# ears_v40.net
KiCad netlist of a schematic drawn in EAGLE
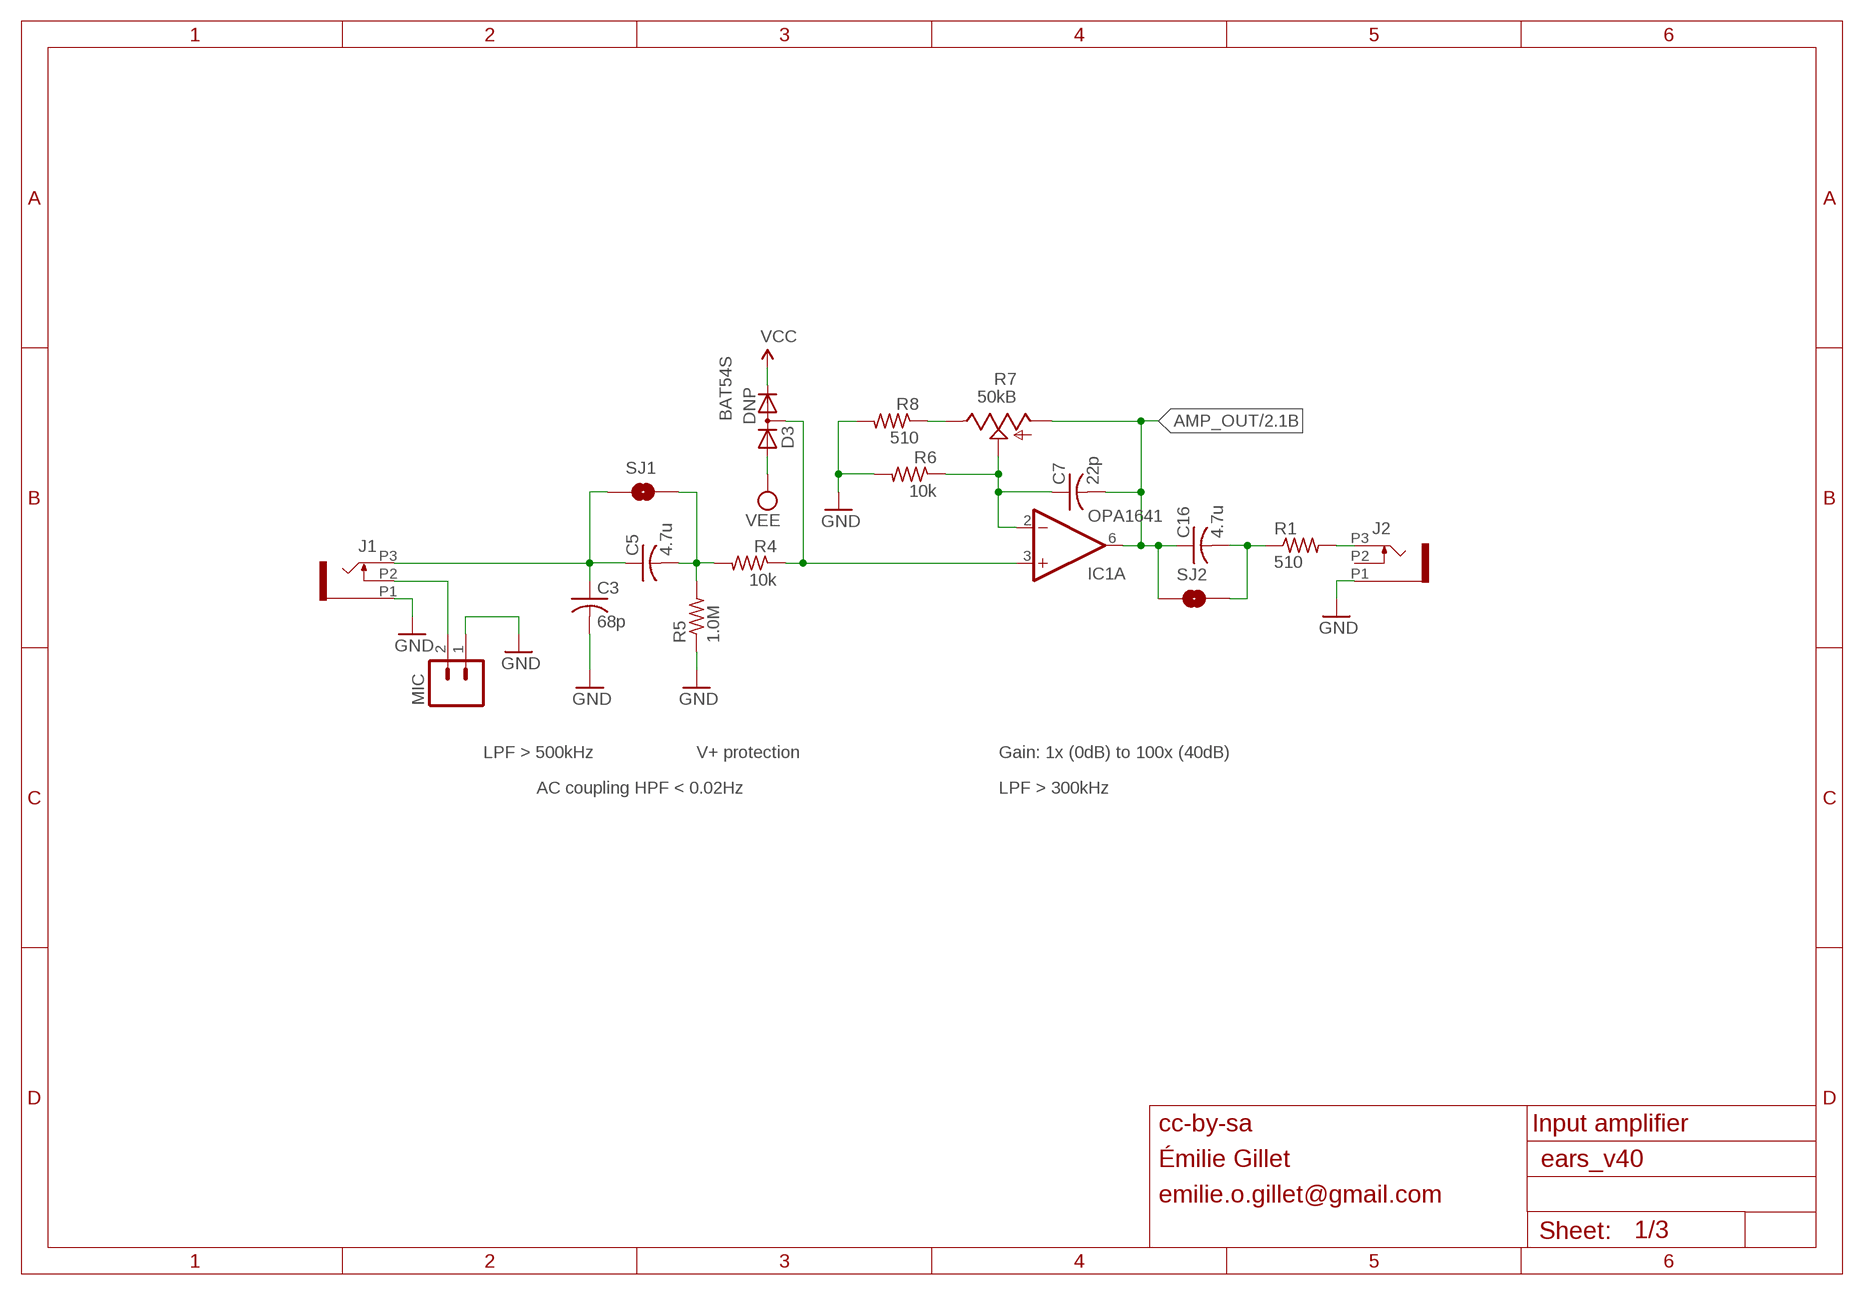
[diagram p0: schematic, sheet 1]
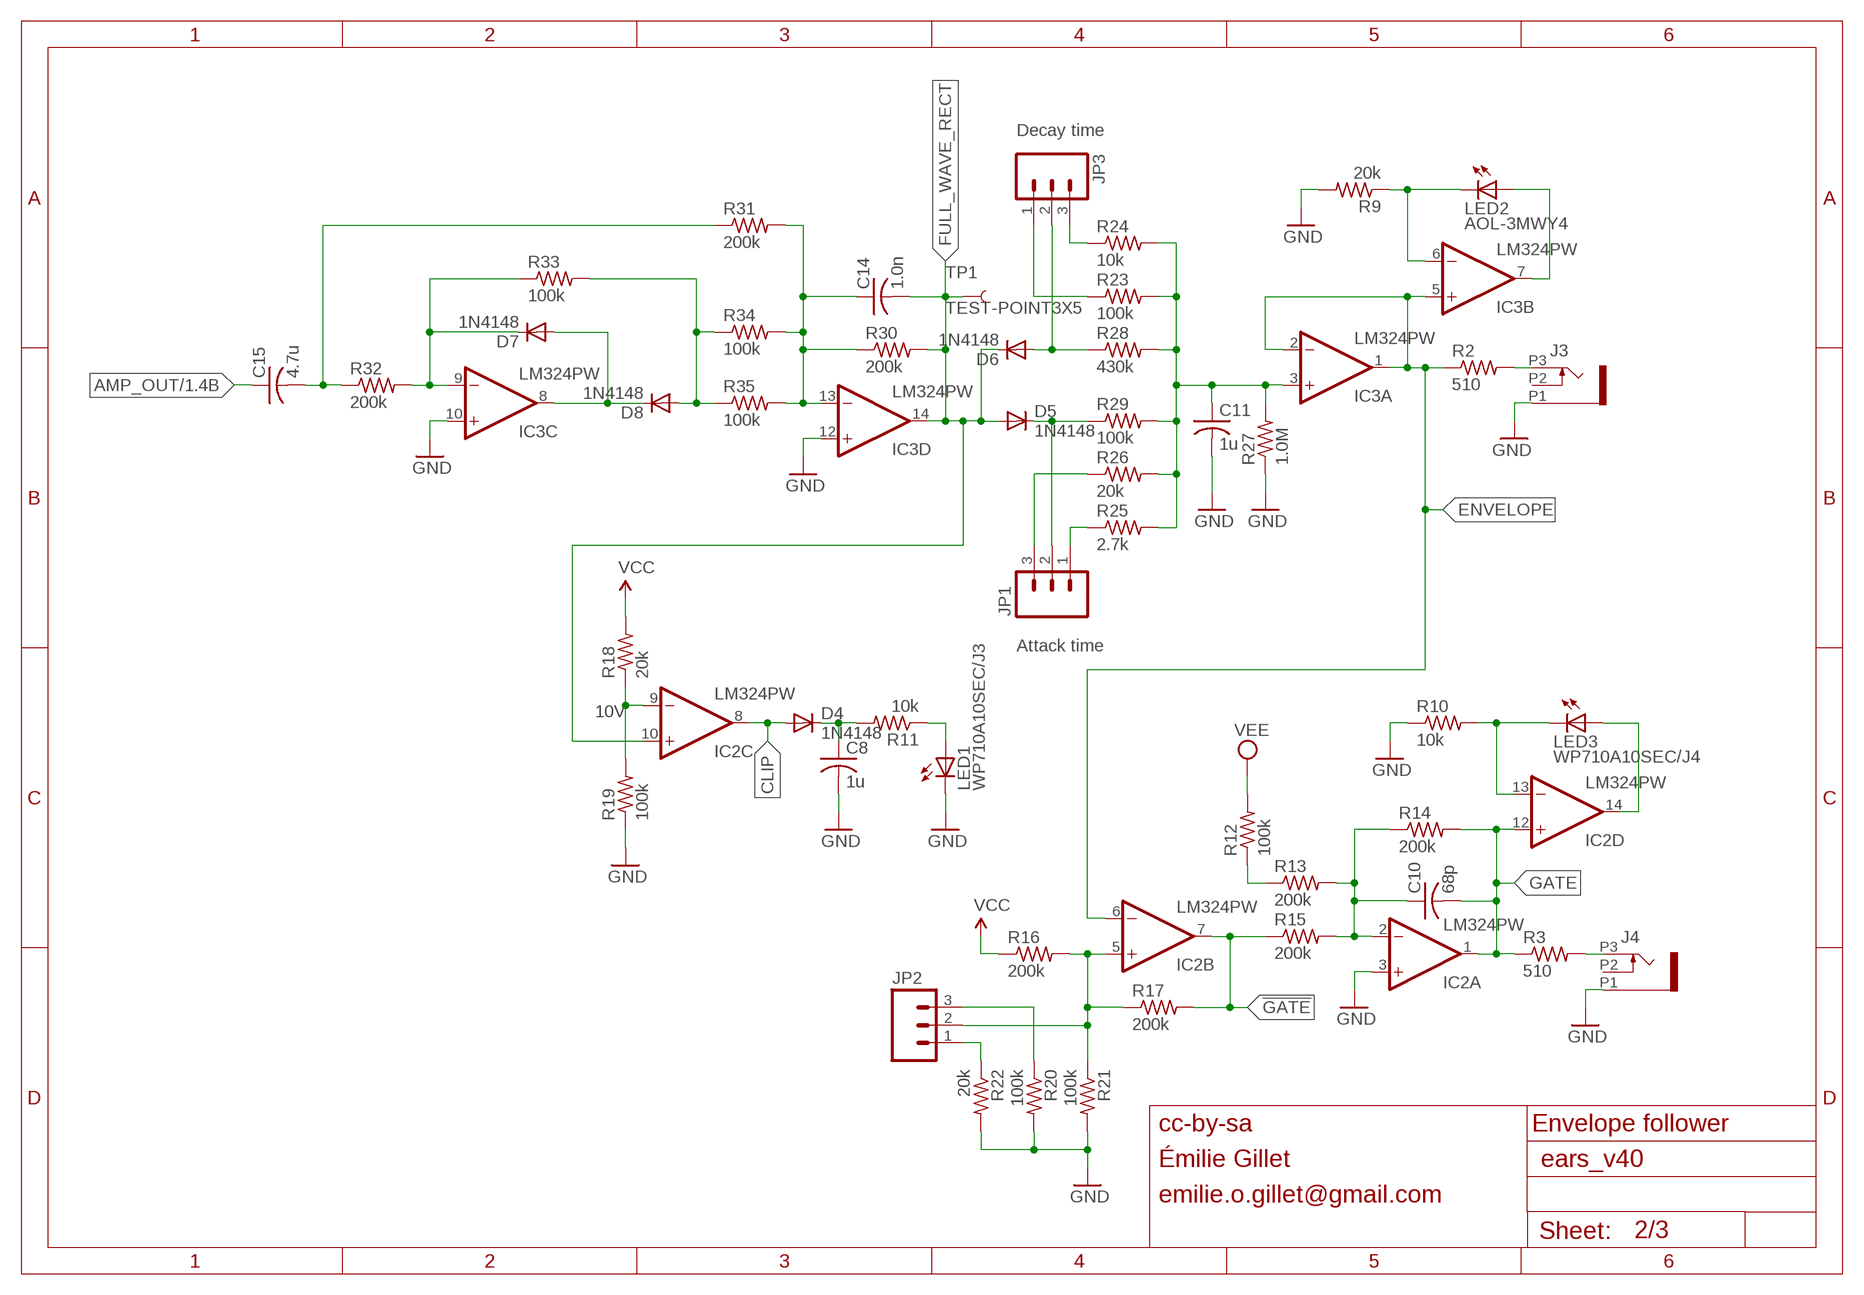
[diagram p1: schematic, sheet 2]
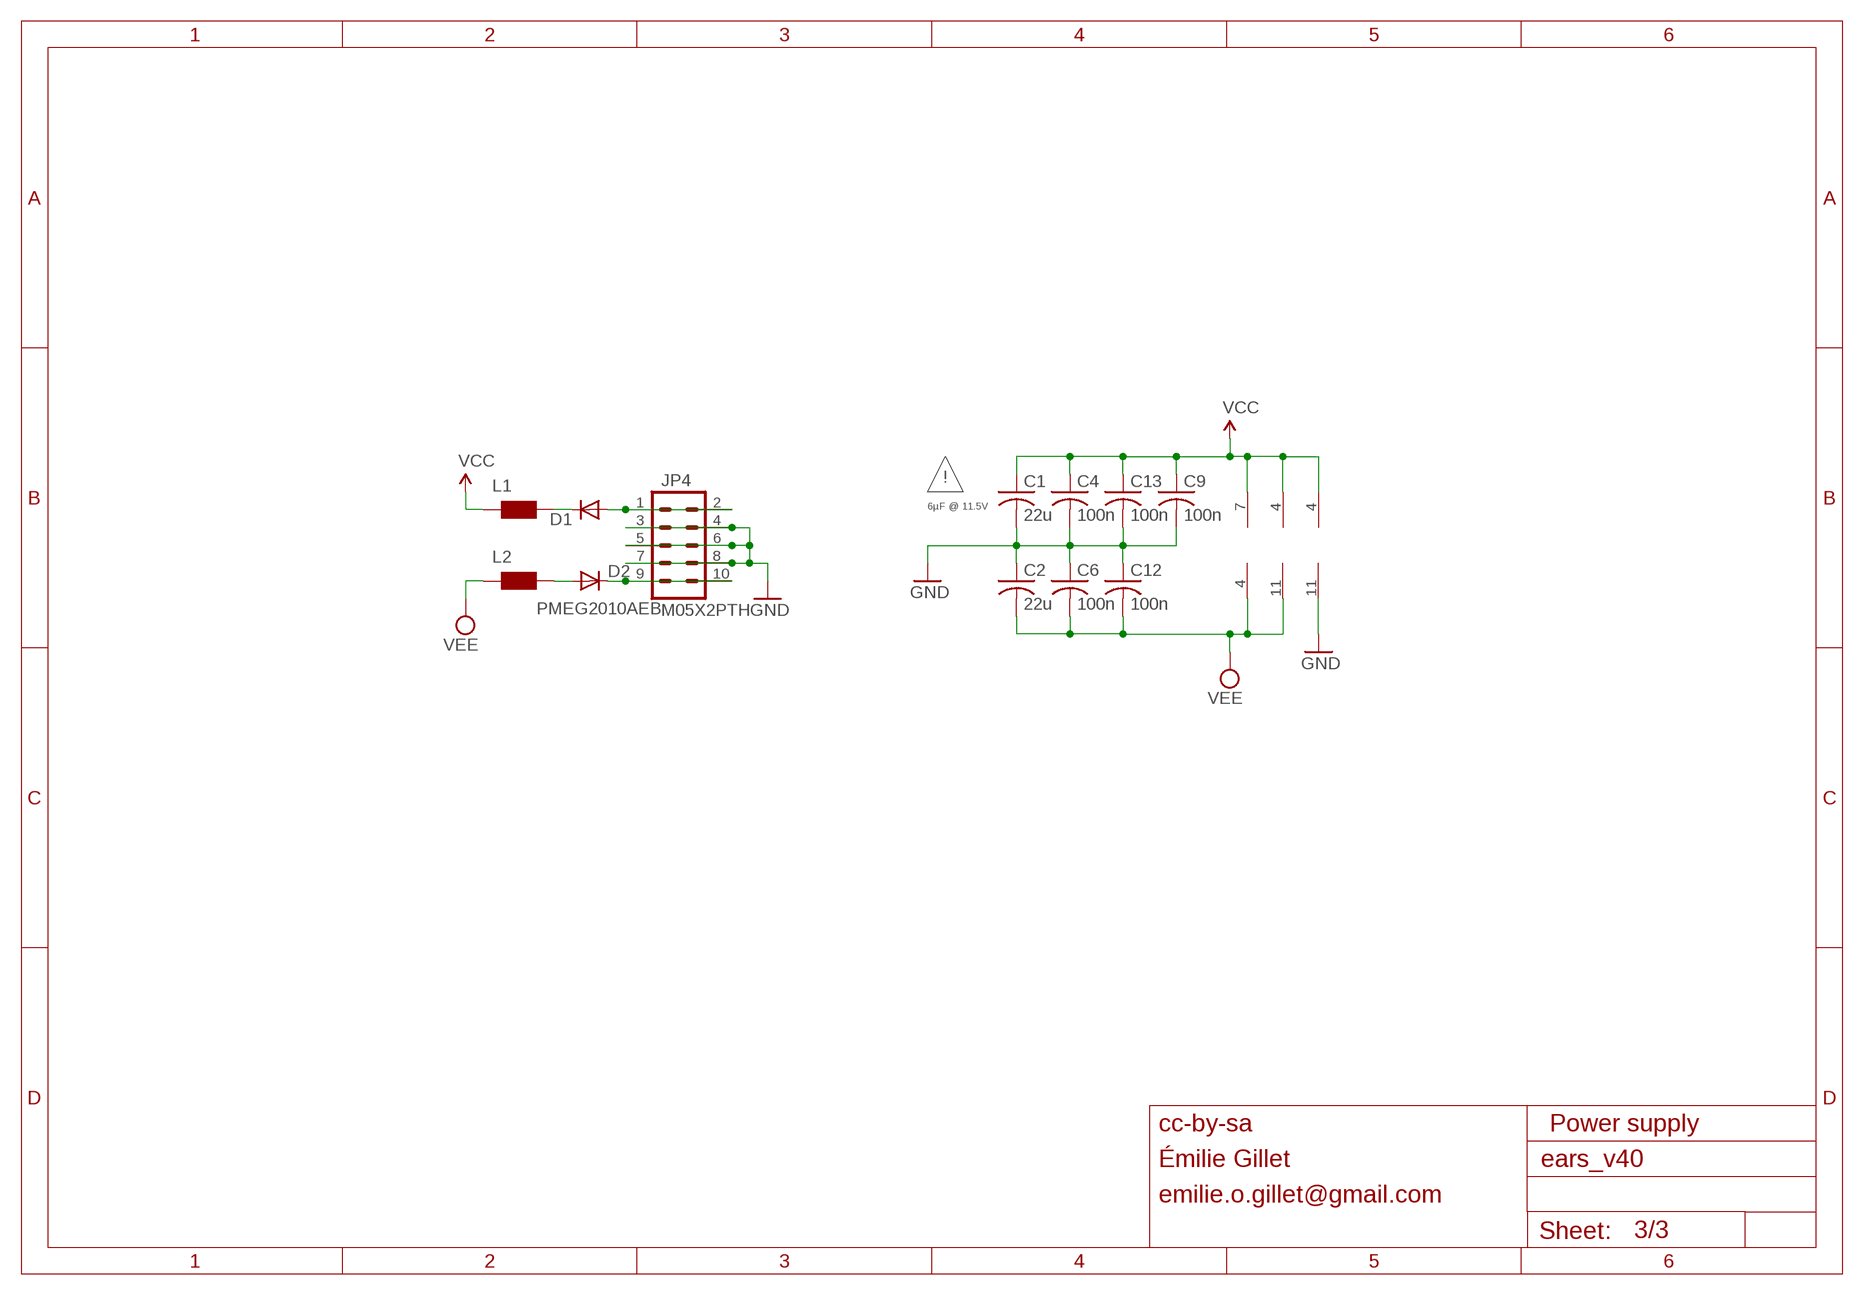
[diagram p2: schematic, sheet 3]

(export (version "E")
  (design (tool "Eeschema 10.0.6"))
  (components
    (comp (ref "C3")
      (value "68p")
      (footprint "eagle-import:C0402")
      (libsource (lib "eagle-import") (part "C-USC0402"))
    )
    (comp (ref "C5")
      (value "4.7u")
      (footprint "eagle-import:C0603")
      (libsource (lib "eagle-import") (part "C-USC0603"))
    )
    (comp (ref "C7")
      (value "22p")
      (footprint "eagle-import:C0402")
      (libsource (lib "eagle-import") (part "C-USC0402"))
    )
    (comp (ref "C16")
      (value "4.7u")
      (footprint "eagle-import:C0603")
      (libsource (lib "eagle-import") (part "C-USC0603"))
    )
    (comp (ref "D3")
      (value "DNP")
      (footprint "eagle-import:SOT23")
      (libsource (lib "eagle-import") (part "DIODE_2CACA-SOT23"))
    )
    (comp (ref "IC1")
      (value "OPA1641")
      (footprint "eagle-import:MSOP8")
      (libsource (lib "eagle-import") (part "OPA1641"))
    )
    (comp (ref "J1")
      (value "PJ301_THONKICONN6")
      (footprint "eagle-import:WQP_PJ_301M6")
      (libsource (lib "eagle-import") (part "PJ301_THONKICONN6"))
    )
    (comp (ref "J2")
      (value "PJ301_THONKICONN6")
      (footprint "eagle-import:WQP_PJ_301M6")
      (libsource (lib "eagle-import") (part "PJ301_THONKICONN6"))
    )
    (comp (ref "MIC")
      (value "M02TINY")
      (footprint "eagle-import:1X02_TINY")
      (libsource (lib "eagle-import") (part "M02TINY"))
    )
    (comp (ref "R1")
      (value "510")
      (footprint "eagle-import:R0402")
      (libsource (lib "eagle-import") (part "R-US_R0402"))
    )
    (comp (ref "R4")
      (value "10k")
      (footprint "eagle-import:R0402")
      (libsource (lib "eagle-import") (part "R-US_R0402"))
    )
    (comp (ref "R5")
      (value "1.0M")
      (footprint "eagle-import:R0402")
      (libsource (lib "eagle-import") (part "R-US_R0402"))
    )
    (comp (ref "R6")
      (value "10k")
      (footprint "eagle-import:R0402")
      (libsource (lib "eagle-import") (part "R-US_R0402"))
    )
    (comp (ref "R7")
      (value "50kB")
      (footprint "eagle-import:ALPS_POT_VERTICAL_PS")
      (libsource (lib "eagle-import") (part "POT_USVERTICAL_PS"))
    )
    (comp (ref "R8")
      (value "510")
      (footprint "eagle-import:R0402")
      (libsource (lib "eagle-import") (part "R-US_R0402"))
    )
    (comp (ref "SJ1")
      (value "SOLDERJUMPERNC")
      (footprint "eagle-import:SJ_2S")
      (libsource (lib "eagle-import") (part "SOLDERJUMPERNC"))
    )
    (comp (ref "SJ2")
      (value "SOLDERJUMPERNC")
      (footprint "eagle-import:SJ_2S")
      (libsource (lib "eagle-import") (part "SOLDERJUMPERNC"))
    )
    (comp (ref "C8")
      (value "1u")
      (footprint "eagle-import:C0402")
      (libsource (lib "eagle-import") (part "C-USC0402"))
    )
    (comp (ref "C10")
      (value "68p")
      (footprint "eagle-import:C0402")
      (libsource (lib "eagle-import") (part "C-USC0402"))
    )
    (comp (ref "C11")
      (value "1u")
      (footprint "eagle-import:C0402")
      (libsource (lib "eagle-import") (part "C-USC0402"))
    )
    (comp (ref "C14")
      (value "1.0n")
      (footprint "eagle-import:C0402")
      (libsource (lib "eagle-import") (part "C-USC0402"))
    )
    (comp (ref "C15")
      (value "4.7u")
      (footprint "eagle-import:C0603")
      (libsource (lib "eagle-import") (part "C-USC0603"))
    )
    (comp (ref "D4")
      (value "1N4148")
      (footprint "eagle-import:SOD523")
      (libsource (lib "eagle-import") (part "DIODE-SOD523"))
    )
    (comp (ref "D5")
      (value "1N4148")
      (footprint "eagle-import:SOD523")
      (libsource (lib "eagle-import") (part "DIODE-SOD523"))
    )
    (comp (ref "D6")
      (value "1N4148")
      (footprint "eagle-import:SOD523")
      (libsource (lib "eagle-import") (part "DIODE-SOD523"))
    )
    (comp (ref "D7")
      (value "1N4148")
      (footprint "eagle-import:SOD523")
      (libsource (lib "eagle-import") (part "DIODE-SOD523"))
    )
    (comp (ref "D8")
      (value "1N4148")
      (footprint "eagle-import:SOD523")
      (libsource (lib "eagle-import") (part "DIODE-SOD523"))
    )
    (comp (ref "IC2")
      (value "LM324PW")
      (footprint "eagle-import:TSSOP14")
      (libsource (lib "eagle-import") (part "LM324PW"))
    )
    (comp (ref "IC3")
      (value "LM324PW")
      (footprint "eagle-import:TSSOP14")
      (libsource (lib "eagle-import") (part "LM324PW"))
    )
    (comp (ref "J3")
      (value "PJ301_THONKICONN6")
      (footprint "eagle-import:WQP_PJ_301M6")
      (libsource (lib "eagle-import") (part "PJ301_THONKICONN6"))
    )
    (comp (ref "J4")
      (value "PJ301_THONKICONN6")
      (footprint "eagle-import:WQP_PJ_301M6")
      (libsource (lib "eagle-import") (part "PJ301_THONKICONN6"))
    )
    (comp (ref "JP1")
      (value "M03PTH")
      (footprint "eagle-import:1X03")
      (libsource (lib "eagle-import") (part "M03PTH"))
    )
    (comp (ref "JP2")
      (value "M03PTH")
      (footprint "eagle-import:1X03")
      (libsource (lib "eagle-import") (part "M03PTH"))
    )
    (comp (ref "JP3")
      (value "M03PTH")
      (footprint "eagle-import:1X03")
      (libsource (lib "eagle-import") (part "M03PTH"))
    )
    (comp (ref "LED1")
      (value "WP710A10SEC/J3")
      (footprint "eagle-import:LED3MM")
      (libsource (lib "eagle-import") (part "LED3MM"))
    )
    (comp (ref "LED2")
      (value "AOL-3MWY4")
      (footprint "eagle-import:LED3MM")
      (libsource (lib "eagle-import") (part "LED3MM"))
    )
    (comp (ref "LED3")
      (value "WP710A10SEC/J4")
      (footprint "eagle-import:LED3MM")
      (libsource (lib "eagle-import") (part "LED3MM"))
    )
    (comp (ref "R2")
      (value "510")
      (footprint "eagle-import:R0402")
      (libsource (lib "eagle-import") (part "R-US_R0402"))
    )
    (comp (ref "R3")
      (value "510")
      (footprint "eagle-import:R0402")
      (libsource (lib "eagle-import") (part "R-US_R0402"))
    )
    (comp (ref "R9")
      (value "20k")
      (footprint "eagle-import:R0402")
      (libsource (lib "eagle-import") (part "R-US_R0402"))
    )
    (comp (ref "R10")
      (value "10k")
      (footprint "eagle-import:R0402")
      (libsource (lib "eagle-import") (part "R-US_R0402"))
    )
    (comp (ref "R11")
      (value "10k")
      (footprint "eagle-import:R0402")
      (libsource (lib "eagle-import") (part "R-US_R0402"))
    )
    (comp (ref "R12")
      (value "100k")
      (footprint "eagle-import:R0402")
      (libsource (lib "eagle-import") (part "R-US_R0402"))
    )
    (comp (ref "R13")
      (value "200k")
      (footprint "eagle-import:R0402")
      (libsource (lib "eagle-import") (part "R-US_R0402"))
    )
    (comp (ref "R14")
      (value "200k")
      (footprint "eagle-import:R0402")
      (libsource (lib "eagle-import") (part "R-US_R0402"))
    )
    (comp (ref "R15")
      (value "200k")
      (footprint "eagle-import:R0402")
      (libsource (lib "eagle-import") (part "R-US_R0402"))
    )
    (comp (ref "R16")
      (value "200k")
      (footprint "eagle-import:R0402")
      (libsource (lib "eagle-import") (part "R-US_R0402"))
    )
    (comp (ref "R17")
      (value "200k")
      (footprint "eagle-import:R0402")
      (libsource (lib "eagle-import") (part "R-US_R0402"))
    )
    (comp (ref "R18")
      (value "20k")
      (footprint "eagle-import:R0402")
      (libsource (lib "eagle-import") (part "R-US_R0402"))
    )
    (comp (ref "R19")
      (value "100k")
      (footprint "eagle-import:R0402")
      (libsource (lib "eagle-import") (part "R-US_R0402"))
    )
    (comp (ref "R20")
      (value "100k")
      (footprint "eagle-import:R0402")
      (libsource (lib "eagle-import") (part "R-US_R0402"))
    )
    (comp (ref "R21")
      (value "100k")
      (footprint "eagle-import:R0402")
      (libsource (lib "eagle-import") (part "R-US_R0402"))
    )
    (comp (ref "R22")
      (value "20k")
      (footprint "eagle-import:R0402")
      (libsource (lib "eagle-import") (part "R-US_R0402"))
    )
    (comp (ref "R23")
      (value "100k")
      (footprint "eagle-import:R0402")
      (libsource (lib "eagle-import") (part "R-US_R0402"))
    )
    (comp (ref "R24")
      (value "10k")
      (footprint "eagle-import:R0402")
      (libsource (lib "eagle-import") (part "R-US_R0402"))
    )
    (comp (ref "R25")
      (value "2.7k")
      (footprint "eagle-import:R0402")
      (libsource (lib "eagle-import") (part "R-US_R0402"))
    )
    (comp (ref "R26")
      (value "20k")
      (footprint "eagle-import:R0402")
      (libsource (lib "eagle-import") (part "R-US_R0402"))
    )
    (comp (ref "R27")
      (value "1.0M")
      (footprint "eagle-import:R0402")
      (libsource (lib "eagle-import") (part "R-US_R0402"))
    )
    (comp (ref "R28")
      (value "430k")
      (footprint "eagle-import:R0402")
      (libsource (lib "eagle-import") (part "R-US_R0402"))
    )
    (comp (ref "R29")
      (value "100k")
      (footprint "eagle-import:R0402")
      (libsource (lib "eagle-import") (part "R-US_R0402"))
    )
    (comp (ref "R30")
      (value "200k")
      (footprint "eagle-import:R0402")
      (libsource (lib "eagle-import") (part "R-US_R0402"))
    )
    (comp (ref "R31")
      (value "200k")
      (footprint "eagle-import:R0402")
      (libsource (lib "eagle-import") (part "R-US_R0402"))
    )
    (comp (ref "R32")
      (value "200k")
      (footprint "eagle-import:R0402")
      (libsource (lib "eagle-import") (part "R-US_R0402"))
    )
    (comp (ref "R33")
      (value "100k")
      (footprint "eagle-import:R0402")
      (libsource (lib "eagle-import") (part "R-US_R0402"))
    )
    (comp (ref "R34")
      (value "100k")
      (footprint "eagle-import:R0402")
      (libsource (lib "eagle-import") (part "R-US_R0402"))
    )
    (comp (ref "R35")
      (value "100k")
      (footprint "eagle-import:R0402")
      (libsource (lib "eagle-import") (part "R-US_R0402"))
    )
    (comp (ref "TP1")
      (value "TEST-POINT3X5")
      (footprint "eagle-import:PAD.03X.05")
      (libsource (lib "eagle-import") (part "TEST-POINT3X5"))
    )
    (comp (ref "C1")
      (value "22u")
      (footprint "eagle-import:C1206")
      (libsource (lib "eagle-import") (part "C-USC1206"))
    )
    (comp (ref "C2")
      (value "22u")
      (footprint "eagle-import:C1206")
      (libsource (lib "eagle-import") (part "C-USC1206"))
    )
    (comp (ref "C4")
      (value "100n")
      (footprint "eagle-import:C0402")
      (libsource (lib "eagle-import") (part "C-USC0402"))
    )
    (comp (ref "C6")
      (value "100n")
      (footprint "eagle-import:C0402")
      (libsource (lib "eagle-import") (part "C-USC0402"))
    )
    (comp (ref "C9")
      (value "100n")
      (footprint "eagle-import:C0402")
      (libsource (lib "eagle-import") (part "C-USC0402"))
    )
    (comp (ref "C12")
      (value "100n")
      (footprint "eagle-import:C0402")
      (libsource (lib "eagle-import") (part "C-USC0402"))
    )
    (comp (ref "C13")
      (value "100n")
      (footprint "eagle-import:C0402")
      (libsource (lib "eagle-import") (part "C-USC0402"))
    )
    (comp (ref "D1")
      (value "PMEG2010AEB")
      (footprint "eagle-import:SOD523")
      (libsource (lib "eagle-import") (part "DIODE-SOD523"))
    )
    (comp (ref "D2")
      (value "PMEG2010AEB")
      (footprint "eagle-import:SOD523")
      (libsource (lib "eagle-import") (part "DIODE-SOD523"))
    )
    (comp (ref "JP4")
      (value "M05X2PTH")
      (footprint "eagle-import:AVR_ICSP")
      (libsource (lib "eagle-import") (part "M05X2PTH"))
    )
    (comp (ref "L1")
      (value "WE-CBF_0603")
      (footprint "eagle-import:0603")
      (libsource (lib "eagle-import") (part "WE-CBF_0603"))
    )
    (comp (ref "L2")
      (value "WE-CBF_0603")
      (footprint "eagle-import:0603")
      (libsource (lib "eagle-import") (part "WE-CBF_0603"))
    )
  )
  (nets
    (net (code "1") (name "AMP_OUT") (class "Default")
      (node (ref "C15") (pin "1") (pinfunction "1_1") (pintype "passive"))
      (node (ref "C16") (pin "1") (pinfunction "1_1") (pintype "passive"))
      (node (ref "C7") (pin "2") (pinfunction "2_2") (pintype "passive"))
      (node (ref "IC1") (pin "6") (pinfunction "OUT_6") (pintype "output"))
      (node (ref "R7") (pin "P$3") (pinfunction "A_P$3") (pintype "passive"))
      (node (ref "SJ2") (pin "1") (pinfunction "1_1") (pintype "passive"))
    )
    (net (code "2") (name "CLIP") (class "Default")
      (node (ref "D4") (pin "A") (pinfunction "A_A") (pintype "passive"))
      (node (ref "IC2") (pin "8") (pinfunction "OUT_8") (pintype "output"))
    )
    (net (code "3") (name "ENVELOPE") (class "Default")
      (node (ref "IC2") (pin "6") (pinfunction "-IN_6") (pintype "input"))
      (node (ref "IC3") (pin "1") (pinfunction "OUT_1") (pintype "output"))
      (node (ref "IC3") (pin "2") (pinfunction "-IN_2") (pintype "input"))
      (node (ref "IC3") (pin "5") (pinfunction "+IN_5") (pintype "input"))
      (node (ref "R2") (pin "1") (pinfunction "1_1") (pintype "passive"))
    )
    (net (code "4") (name "FULL_WAVE_RECT") (class "Default")
      (node (ref "C14") (pin "2") (pinfunction "2_2") (pintype "passive"))
      (node (ref "D5") (pin "A") (pinfunction "A_A") (pintype "passive"))
      (node (ref "D6") (pin "C") (pinfunction "C_C") (pintype "passive"))
      (node (ref "IC2") (pin "10") (pinfunction "+IN_10") (pintype "input"))
      (node (ref "IC3") (pin "14") (pinfunction "OUT_14") (pintype "output"))
      (node (ref "R30") (pin "2") (pinfunction "2_2") (pintype "passive"))
      (node (ref "TP1") (pin "P$1") (pinfunction "1_P$1") (pintype "bidirectional"))
    )
    (net (code "5") (name "GATE") (class "Default")
      (node (ref "C10") (pin "2") (pinfunction "2_2") (pintype "passive"))
      (node (ref "IC2") (pin "1") (pinfunction "OUT_1") (pintype "output"))
      (node (ref "IC2") (pin "12") (pinfunction "+IN_12") (pintype "input"))
      (node (ref "R14") (pin "2") (pinfunction "2_2") (pintype "passive"))
      (node (ref "R3") (pin "1") (pinfunction "1_1") (pintype "passive"))
    )
    (net (code "6") (name "GND") (class "Default")
      (node (ref "C1") (pin "2") (pinfunction "2_2") (pintype "passive"))
      (node (ref "C11") (pin "2") (pinfunction "2_2") (pintype "passive"))
      (node (ref "C12") (pin "1") (pinfunction "1_1") (pintype "passive"))
      (node (ref "C13") (pin "2") (pinfunction "2_2") (pintype "passive"))
      (node (ref "C2") (pin "1") (pinfunction "1_1") (pintype "passive"))
      (node (ref "C3") (pin "2") (pinfunction "2_2") (pintype "passive"))
      (node (ref "C4") (pin "2") (pinfunction "2_2") (pintype "passive"))
      (node (ref "C6") (pin "1") (pinfunction "1_1") (pintype "passive"))
      (node (ref "C8") (pin "2") (pinfunction "2_2") (pintype "passive"))
      (node (ref "C9") (pin "2") (pinfunction "2_2") (pintype "passive"))
      (node (ref "IC2") (pin "11") (pinfunction "V-_11") (pintype "power_in"))
      (node (ref "IC2") (pin "3") (pinfunction "+IN_3") (pintype "input"))
      (node (ref "IC3") (pin "10") (pinfunction "+IN_10") (pintype "input"))
      (node (ref "IC3") (pin "12") (pinfunction "+IN_12") (pintype "input"))
      (node (ref "J1") (pin "P1") (pinfunction "1_P1") (pintype "passive"))
      (node (ref "J2") (pin "P1") (pinfunction "1_P1") (pintype "passive"))
      (node (ref "J3") (pin "P1") (pinfunction "1_P1") (pintype "passive"))
      (node (ref "J4") (pin "P1") (pinfunction "1_P1") (pintype "passive"))
      (node (ref "JP4") (pin "3") (pinfunction "3_3") (pintype "passive"))
      (node (ref "JP4") (pin "4") (pinfunction "4_4") (pintype "passive"))
      (node (ref "JP4") (pin "5") (pinfunction "5_5") (pintype "passive"))
      (node (ref "JP4") (pin "6") (pinfunction "6_6") (pintype "passive"))
      (node (ref "JP4") (pin "7") (pinfunction "7_7") (pintype "passive"))
      (node (ref "JP4") (pin "8") (pinfunction "8_8") (pintype "passive"))
      (node (ref "LED1") (pin "K") (pinfunction "C_K") (pintype "passive"))
      (node (ref "MIC") (pin "1") (pinfunction "1_1") (pintype "passive"))
      (node (ref "R10") (pin "1") (pinfunction "1_1") (pintype "passive"))
      (node (ref "R19") (pin "1") (pinfunction "1_1") (pintype "passive"))
      (node (ref "R20") (pin "2") (pinfunction "2_2") (pintype "passive"))
      (node (ref "R21") (pin "2") (pinfunction "2_2") (pintype "passive"))
      (node (ref "R22") (pin "2") (pinfunction "2_2") (pintype "passive"))
      (node (ref "R27") (pin "1") (pinfunction "1_1") (pintype "passive"))
      (node (ref "R5") (pin "1") (pinfunction "1_1") (pintype "passive"))
      (node (ref "R6") (pin "2") (pinfunction "2_2") (pintype "passive"))
      (node (ref "R8") (pin "2") (pinfunction "2_2") (pintype "passive"))
      (node (ref "R9") (pin "2") (pinfunction "2_2") (pintype "passive"))
    )
    (net (code "7") (name "Net-(C5-Pad2)") (class "Default")
      (node (ref "C5") (pin "2") (pinfunction "2_2") (pintype "passive"))
      (node (ref "R4") (pin "2") (pinfunction "2_2") (pintype "passive"))
      (node (ref "R5") (pin "2") (pinfunction "2_2") (pintype "passive"))
      (node (ref "SJ1") (pin "2") (pinfunction "2_2") (pintype "passive"))
    )
    (net (code "8") (name "Net-(C8-Pad1)") (class "Default")
      (node (ref "C8") (pin "1") (pinfunction "1_1") (pintype "passive"))
      (node (ref "D4") (pin "C") (pinfunction "C_C") (pintype "passive"))
      (node (ref "R11") (pin "2") (pinfunction "2_2") (pintype "passive"))
    )
    (net (code "9") (name "Net-(C15-Pad2)") (class "Default")
      (node (ref "C15") (pin "2") (pinfunction "2_2") (pintype "passive"))
      (node (ref "R31") (pin "1") (pinfunction "1_1") (pintype "passive"))
      (node (ref "R32") (pin "1") (pinfunction "1_1") (pintype "passive"))
    )
    (net (code "10") (name "Net-(C16-Pad2)") (class "Default")
      (node (ref "C16") (pin "2") (pinfunction "2_2") (pintype "passive"))
      (node (ref "R1") (pin "1") (pinfunction "1_1") (pintype "passive"))
      (node (ref "SJ2") (pin "2") (pinfunction "2_2") (pintype "passive"))
    )
    (net (code "11") (name "Net-(D1-PadA)") (class "Default")
      (node (ref "D1") (pin "A") (pinfunction "A_A") (pintype "passive"))
      (node (ref "JP4") (pin "1") (pinfunction "1_1") (pintype "passive"))
      (node (ref "JP4") (pin "2") (pinfunction "2_2") (pintype "passive"))
    )
    (net (code "12") (name "Net-(D1-PadC)") (class "Default")
      (node (ref "D1") (pin "C") (pinfunction "C_C") (pintype "passive"))
      (node (ref "L1") (pin "2") (pinfunction "2_2") (pintype "passive"))
    )
    (net (code "13") (name "Net-(D2-PadA)") (class "Default")
      (node (ref "D2") (pin "A") (pinfunction "A_A") (pintype "passive"))
      (node (ref "L2") (pin "2") (pinfunction "2_2") (pintype "passive"))
    )
    (net (code "14") (name "Net-(D2-PadC)") (class "Default")
      (node (ref "D2") (pin "C") (pinfunction "C_C") (pintype "passive"))
      (node (ref "JP4") (pin "10") (pinfunction "10_10") (pintype "passive"))
      (node (ref "JP4") (pin "9") (pinfunction "9_9") (pintype "passive"))
    )
    (net (code "15") (name "Net-(D3-AC)") (class "Default")
      (node (ref "D3") (pin "3") (pinfunction "AC_3") (pintype "passive"))
      (node (ref "IC1") (pin "3") (pinfunction "+IN_3") (pintype "input"))
      (node (ref "R4") (pin "1") (pinfunction "1_1") (pintype "passive"))
    )
    (net (code "16") (name "Net-(D5-PadC)") (class "Default")
      (node (ref "D5") (pin "C") (pinfunction "C_C") (pintype "passive"))
      (node (ref "JP1") (pin "2") (pinfunction "2_2") (pintype "passive"))
      (node (ref "R29") (pin "1") (pinfunction "1_1") (pintype "passive"))
    )
    (net (code "17") (name "Net-(D6-PadA)") (class "Default")
      (node (ref "D6") (pin "A") (pinfunction "A_A") (pintype "passive"))
      (node (ref "JP3") (pin "2") (pinfunction "2_2") (pintype "passive"))
      (node (ref "R28") (pin "1") (pinfunction "1_1") (pintype "passive"))
    )
    (net (code "18") (name "Net-(D8-PadA)") (class "Default")
      (node (ref "D8") (pin "A") (pinfunction "A_A") (pintype "passive"))
      (node (ref "R33") (pin "2") (pinfunction "2_2") (pintype "passive"))
      (node (ref "R34") (pin "1") (pinfunction "1_1") (pintype "passive"))
      (node (ref "R35") (pin "1") (pinfunction "1_1") (pintype "passive"))
    )
    (net (code "19") (name "Net-(IC1A--IN)") (class "Default")
      (node (ref "C7") (pin "1") (pinfunction "1_1") (pintype "passive"))
      (node (ref "IC1") (pin "2") (pinfunction "-IN_2") (pintype "input"))
      (node (ref "R6") (pin "1") (pinfunction "1_1") (pintype "passive"))
      (node (ref "R7") (pin "P$2") (pinfunction "S_P$2") (pintype "passive"))
    )
    (net (code "20") (name "Net-(IC2A--IN)") (class "Default")
      (node (ref "C10") (pin "1") (pinfunction "1_1") (pintype "passive"))
      (node (ref "IC2") (pin "2") (pinfunction "-IN_2") (pintype "input"))
      (node (ref "R13") (pin "2") (pinfunction "2_2") (pintype "passive"))
      (node (ref "R14") (pin "1") (pinfunction "1_1") (pintype "passive"))
      (node (ref "R15") (pin "2") (pinfunction "2_2") (pintype "passive"))
    )
    (net (code "21") (name "Net-(IC2B-+IN)") (class "Default")
      (node (ref "IC2") (pin "5") (pinfunction "+IN_5") (pintype "input"))
      (node (ref "JP2") (pin "2") (pinfunction "2_2") (pintype "passive"))
      (node (ref "R16") (pin "2") (pinfunction "2_2") (pintype "passive"))
      (node (ref "R17") (pin "1") (pinfunction "1_1") (pintype "passive"))
      (node (ref "R21") (pin "1") (pinfunction "1_1") (pintype "passive"))
    )
    (net (code "22") (name "Net-(IC2C--IN)") (class "Default")
      (node (ref "IC2") (pin "9") (pinfunction "-IN_9") (pintype "input"))
      (node (ref "R18") (pin "1") (pinfunction "1_1") (pintype "passive"))
      (node (ref "R19") (pin "2") (pinfunction "2_2") (pintype "passive"))
    )
    (net (code "23") (name "Net-(IC2D--IN)") (class "Default")
      (node (ref "IC2") (pin "13") (pinfunction "-IN_13") (pintype "input"))
      (node (ref "LED3") (pin "K") (pinfunction "C_K") (pintype "passive"))
      (node (ref "R10") (pin "2") (pinfunction "2_2") (pintype "passive"))
    )
    (net (code "24") (name "Net-(IC2D-OUT)") (class "Default")
      (node (ref "IC2") (pin "14") (pinfunction "OUT_14") (pintype "output"))
      (node (ref "LED3") (pin "A") (pinfunction "A_A") (pintype "passive"))
    )
    (net (code "25") (name "Net-(IC3A-+IN)") (class "Default")
      (node (ref "C11") (pin "1") (pinfunction "1_1") (pintype "passive"))
      (node (ref "IC3") (pin "3") (pinfunction "+IN_3") (pintype "input"))
      (node (ref "R23") (pin "2") (pinfunction "2_2") (pintype "passive"))
      (node (ref "R24") (pin "2") (pinfunction "2_2") (pintype "passive"))
      (node (ref "R25") (pin "2") (pinfunction "2_2") (pintype "passive"))
      (node (ref "R26") (pin "2") (pinfunction "2_2") (pintype "passive"))
      (node (ref "R27") (pin "2") (pinfunction "2_2") (pintype "passive"))
      (node (ref "R28") (pin "2") (pinfunction "2_2") (pintype "passive"))
      (node (ref "R29") (pin "2") (pinfunction "2_2") (pintype "passive"))
    )
    (net (code "26") (name "Net-(IC3B--IN)") (class "Default")
      (node (ref "IC3") (pin "6") (pinfunction "-IN_6") (pintype "input"))
      (node (ref "LED2") (pin "K") (pinfunction "C_K") (pintype "passive"))
      (node (ref "R9") (pin "1") (pinfunction "1_1") (pintype "passive"))
    )
    (net (code "27") (name "Net-(IC3B-OUT)") (class "Default")
      (node (ref "IC3") (pin "7") (pinfunction "OUT_7") (pintype "output"))
      (node (ref "LED2") (pin "A") (pinfunction "A_A") (pintype "passive"))
    )
    (net (code "28") (name "Net-(IC3C--IN)") (class "Default")
      (node (ref "D7") (pin "C") (pinfunction "C_C") (pintype "passive"))
      (node (ref "IC3") (pin "9") (pinfunction "-IN_9") (pintype "input"))
      (node (ref "R32") (pin "2") (pinfunction "2_2") (pintype "passive"))
      (node (ref "R33") (pin "1") (pinfunction "1_1") (pintype "passive"))
    )
    (net (code "29") (name "Net-(IC3C-OUT)") (class "Default")
      (node (ref "D7") (pin "A") (pinfunction "A_A") (pintype "passive"))
      (node (ref "D8") (pin "C") (pinfunction "C_C") (pintype "passive"))
      (node (ref "IC3") (pin "8") (pinfunction "OUT_8") (pintype "output"))
    )
    (net (code "30") (name "Net-(IC3D--IN)") (class "Default")
      (node (ref "C14") (pin "1") (pinfunction "1_1") (pintype "passive"))
      (node (ref "IC3") (pin "13") (pinfunction "-IN_13") (pintype "input"))
      (node (ref "R30") (pin "1") (pinfunction "1_1") (pintype "passive"))
      (node (ref "R31") (pin "2") (pinfunction "2_2") (pintype "passive"))
      (node (ref "R34") (pin "2") (pinfunction "2_2") (pintype "passive"))
      (node (ref "R35") (pin "2") (pinfunction "2_2") (pintype "passive"))
    )
    (net (code "31") (name "Net-(J1-2)") (class "Default")
      (node (ref "J1") (pin "P2") (pinfunction "2_P2") (pintype "passive"))
      (node (ref "MIC") (pin "2") (pinfunction "2_2") (pintype "passive"))
    )
    (net (code "32") (name "Net-(J1-3)") (class "Default")
      (node (ref "C3") (pin "1") (pinfunction "1_1") (pintype "passive"))
      (node (ref "C5") (pin "1") (pinfunction "1_1") (pintype "passive"))
      (node (ref "J1") (pin "P3") (pinfunction "3_P3") (pintype "passive"))
      (node (ref "SJ1") (pin "1") (pinfunction "1_1") (pintype "passive"))
    )
    (net (code "33") (name "Net-(J2-3)") (class "Default")
      (node (ref "J2") (pin "P3") (pinfunction "3_P3") (pintype "passive"))
      (node (ref "R1") (pin "2") (pinfunction "2_2") (pintype "passive"))
    )
    (net (code "34") (name "Net-(J3-3)") (class "Default")
      (node (ref "J3") (pin "P3") (pinfunction "3_P3") (pintype "passive"))
      (node (ref "R2") (pin "2") (pinfunction "2_2") (pintype "passive"))
    )
    (net (code "35") (name "Net-(J4-3)") (class "Default")
      (node (ref "J4") (pin "P3") (pinfunction "3_P3") (pintype "passive"))
      (node (ref "R3") (pin "2") (pinfunction "2_2") (pintype "passive"))
    )
    (net (code "36") (name "Net-(JP1-Pad1)") (class "Default")
      (node (ref "JP1") (pin "1") (pinfunction "1_1") (pintype "passive"))
      (node (ref "R25") (pin "1") (pinfunction "1_1") (pintype "passive"))
    )
    (net (code "37") (name "Net-(JP1-Pad3)") (class "Default")
      (node (ref "JP1") (pin "3") (pinfunction "3_3") (pintype "passive"))
      (node (ref "R26") (pin "1") (pinfunction "1_1") (pintype "passive"))
    )
    (net (code "38") (name "Net-(JP2-Pad1)") (class "Default")
      (node (ref "JP2") (pin "1") (pinfunction "1_1") (pintype "passive"))
      (node (ref "R22") (pin "1") (pinfunction "1_1") (pintype "passive"))
    )
    (net (code "39") (name "Net-(JP2-Pad3)") (class "Default")
      (node (ref "JP2") (pin "3") (pinfunction "3_3") (pintype "passive"))
      (node (ref "R20") (pin "1") (pinfunction "1_1") (pintype "passive"))
    )
    (net (code "40") (name "Net-(JP3-Pad1)") (class "Default")
      (node (ref "JP3") (pin "1") (pinfunction "1_1") (pintype "passive"))
      (node (ref "R23") (pin "1") (pinfunction "1_1") (pintype "passive"))
    )
    (net (code "41") (name "Net-(JP3-Pad3)") (class "Default")
      (node (ref "JP3") (pin "3") (pinfunction "3_3") (pintype "passive"))
      (node (ref "R24") (pin "1") (pinfunction "1_1") (pintype "passive"))
    )
    (net (code "42") (name "Net-(LED1-PadA)") (class "Default")
      (node (ref "LED1") (pin "A") (pinfunction "A_A") (pintype "passive"))
      (node (ref "R11") (pin "1") (pinfunction "1_1") (pintype "passive"))
    )
    (net (code "43") (name "Net-(R7-E)") (class "Default")
      (node (ref "R7") (pin "P$1") (pinfunction "E_P$1") (pintype "passive"))
      (node (ref "R8") (pin "1") (pinfunction "1_1") (pintype "passive"))
    )
    (net (code "44") (name "Net-(R12-Pad1)") (class "Default")
      (node (ref "R12") (pin "1") (pinfunction "1_1") (pintype "passive"))
      (node (ref "R13") (pin "1") (pinfunction "1_1") (pintype "passive"))
    )
    (net (code "45") (name "VCC") (class "Default")
      (node (ref "C1") (pin "1") (pinfunction "1_1") (pintype "passive"))
      (node (ref "C13") (pin "1") (pinfunction "1_1") (pintype "passive"))
      (node (ref "C4") (pin "1") (pinfunction "1_1") (pintype "passive"))
      (node (ref "C9") (pin "1") (pinfunction "1_1") (pintype "passive"))
      (node (ref "D3") (pin "2") (pinfunction "C_2") (pintype "passive"))
      (node (ref "IC1") (pin "7") (pinfunction "V+_7") (pintype "power_in"))
      (node (ref "IC2") (pin "4") (pinfunction "V+_4") (pintype "power_in"))
      (node (ref "IC3") (pin "4") (pinfunction "V+_4") (pintype "power_in"))
      (node (ref "L1") (pin "1") (pinfunction "1_1") (pintype "passive"))
      (node (ref "R16") (pin "1") (pinfunction "1_1") (pintype "passive"))
      (node (ref "R18") (pin "2") (pinfunction "2_2") (pintype "passive"))
    )
    (net (code "46") (name "VEE") (class "Default")
      (node (ref "C12") (pin "2") (pinfunction "2_2") (pintype "passive"))
      (node (ref "C2") (pin "2") (pinfunction "2_2") (pintype "passive"))
      (node (ref "C6") (pin "2") (pinfunction "2_2") (pintype "passive"))
      (node (ref "D3") (pin "1") (pinfunction "A_1") (pintype "passive"))
      (node (ref "IC1") (pin "4") (pinfunction "V-_4") (pintype "power_in"))
      (node (ref "IC3") (pin "11") (pinfunction "V-_11") (pintype "power_in"))
      (node (ref "L2") (pin "1") (pinfunction "1_1") (pintype "passive"))
      (node (ref "R12") (pin "2") (pinfunction "2_2") (pintype "passive"))
    )
    (net (code "47") (name "unconnected-(J2-2-PadP2)") (class "Default")
      (node (ref "J2") (pin "P2") (pinfunction "2_P2") (pintype "passive"))
    )
    (net (code "48") (name "unconnected-(J3-2-PadP2)") (class "Default")
      (node (ref "J3") (pin "P2") (pinfunction "2_P2") (pintype "passive"))
    )
    (net (code "49") (name "unconnected-(J4-2-PadP2)") (class "Default")
      (node (ref "J4") (pin "P2") (pinfunction "2_P2") (pintype "passive"))
    )
    (net (code "50") (name "~{GATE}") (class "Default")
      (node (ref "IC2") (pin "7") (pinfunction "OUT_7") (pintype "output"))
      (node (ref "R15") (pin "1") (pinfunction "1_1") (pintype "passive"))
      (node (ref "R17") (pin "2") (pinfunction "2_2") (pintype "passive"))
    )
  )
)
